# schematic.net
KiCad netlist of a schematic drawn in EAGLE
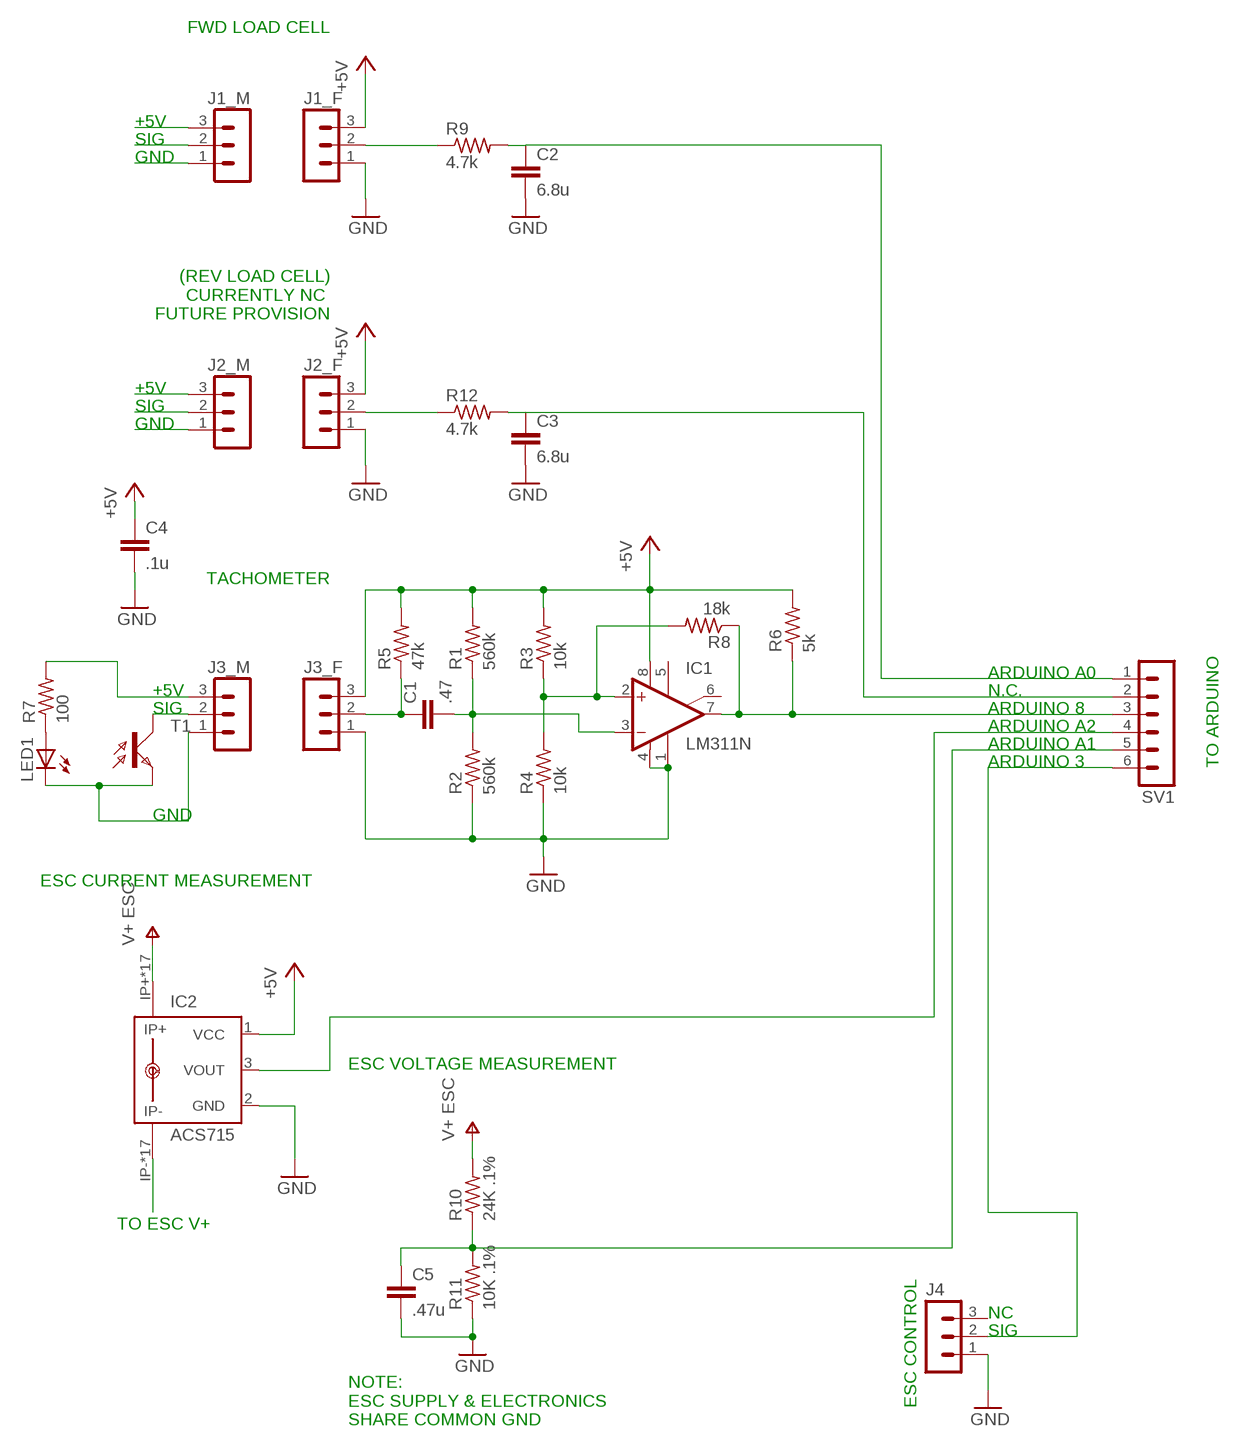
[diagram p0: schematic, sheet 1]

(export (version "E")
  (design (tool "Eeschema 10.0.6"))
  (components
    (comp (ref "C1")
      (value ".47")
      (footprint "eagle-import:C7.5B4")
      (libsource (lib "eagle-import") (part "C7.5/4"))
    )
    (comp (ref "C2")
      (value "6.8u")
      (footprint "eagle-import:C7.5B4")
      (libsource (lib "eagle-import") (part "C7.5/4"))
    )
    (comp (ref "C3")
      (value "6.8u")
      (footprint "eagle-import:C7.5B4")
      (libsource (lib "eagle-import") (part "C7.5/4"))
    )
    (comp (ref "C4")
      (value ".1u")
      (footprint "eagle-import:C7.5B4")
      (libsource (lib "eagle-import") (part "C7.5/4"))
    )
    (comp (ref "C5")
      (value ".47u")
      (footprint "eagle-import:C7.5B4")
      (libsource (lib "eagle-import") (part "C7.5/4"))
    )
    (comp (ref "IC1")
      (value "LM311N")
      (footprint "eagle-import:DIL08")
      (libsource (lib "eagle-import") (part "LM311N"))
    )
    (comp (ref "IC2")
      (value "ACS715")
      (footprint "eagle-import:ACS75050")
      (fields (field (name "MF") "ALLEGRO MICROSYSTEMS, INC.") (field (name "MPN") "ACS750LCA-050"))
      (libsource (lib "eagle-import") (part "ACS750CA-050L"))
    )
    (comp (ref "J1_F")
      (value "MA03-1")
      (footprint "eagle-import:MA03-1")
      (libsource (lib "eagle-import") (part "MA03-1"))
    )
    (comp (ref "J1_M")
      (value "MA03-1")
      (footprint "eagle-import:MA03-1")
      (libsource (lib "eagle-import") (part "MA03-1"))
    )
    (comp (ref "J2_F")
      (value "MA03-1")
      (footprint "eagle-import:MA03-1")
      (libsource (lib "eagle-import") (part "MA03-1"))
    )
    (comp (ref "J2_M")
      (value "MA03-1")
      (footprint "eagle-import:MA03-1")
      (libsource (lib "eagle-import") (part "MA03-1"))
    )
    (comp (ref "J3_F")
      (value "MA03-1")
      (footprint "eagle-import:MA03-1")
      (libsource (lib "eagle-import") (part "MA03-1"))
    )
    (comp (ref "J3_M")
      (value "MA03-1")
      (footprint "eagle-import:MA03-1")
      (libsource (lib "eagle-import") (part "MA03-1"))
    )
    (comp (ref "J4")
      (value "MA03-1")
      (footprint "eagle-import:MA03-1")
      (libsource (lib "eagle-import") (part "MA03-1"))
    )
    (comp (ref "LED1")
      (value "LAP4-BOTTOM")
      (footprint "eagle-import:P47F-BOTTOM")
      (libsource (lib "eagle-import") (part "P4-BOTTOMLA"))
    )
    (comp (ref "R1")
      (value "560k")
      (footprint "eagle-import:0207_10")
      (libsource (lib "eagle-import") (part "R-US_0207/10"))
    )
    (comp (ref "R2")
      (value "560k")
      (footprint "eagle-import:0207_10")
      (libsource (lib "eagle-import") (part "R-US_0207/10"))
    )
    (comp (ref "R3")
      (value "10k")
      (footprint "eagle-import:0207_10")
      (libsource (lib "eagle-import") (part "R-US_0207/10"))
    )
    (comp (ref "R4")
      (value "10k")
      (footprint "eagle-import:0207_10")
      (libsource (lib "eagle-import") (part "R-US_0207/10"))
    )
    (comp (ref "R5")
      (value "47k")
      (footprint "eagle-import:0207_10")
      (libsource (lib "eagle-import") (part "R-US_0207/10"))
    )
    (comp (ref "R6")
      (value "5k")
      (footprint "eagle-import:0207_10")
      (libsource (lib "eagle-import") (part "R-US_0207/10"))
    )
    (comp (ref "R7")
      (value "100")
      (footprint "eagle-import:0207_10")
      (libsource (lib "eagle-import") (part "R-US_0207/10"))
    )
    (comp (ref "R8")
      (value "18k")
      (footprint "eagle-import:0207_10")
      (libsource (lib "eagle-import") (part "R-US_0207/10"))
    )
    (comp (ref "R9")
      (value "4.7k")
      (footprint "eagle-import:0207_10")
      (libsource (lib "eagle-import") (part "R-US_0207/10"))
    )
    (comp (ref "R10")
      (value "24K .1%")
      (footprint "eagle-import:0207_10")
      (libsource (lib "eagle-import") (part "R-US_0207/10"))
    )
    (comp (ref "R11")
      (value "10K .1%")
      (footprint "eagle-import:0207_10")
      (libsource (lib "eagle-import") (part "R-US_0207/10"))
    )
    (comp (ref "R12")
      (value "4.7k")
      (footprint "eagle-import:0207_10")
      (libsource (lib "eagle-import") (part "R-US_0207/10"))
    )
    (comp (ref "SV1")
      (value "MA06-1")
      (footprint "eagle-import:MA06-1")
      (libsource (lib "eagle-import") (part "MA06-1"))
    )
    (comp (ref "T1")
      (value "BPX81")
      (footprint "eagle-import:BPX81")
      (libsource (lib "eagle-import") (part "BPX81"))
    )
  )
  (nets
    (net (code "1") (name "+5V") (class "Default")
      (node (ref "C4") (pin "1") (pinfunction "1_1") (pintype "passive"))
      (node (ref "IC1") (pin "8") (pinfunction "V+_8") (pintype "power_in"))
      (node (ref "IC2") (pin "1") (pinfunction "VCC_1") (pintype "power_in"))
      (node (ref "J1_F") (pin "3") (pinfunction "3_3") (pintype "passive"))
      (node (ref "J2_F") (pin "3") (pinfunction "3_3") (pintype "passive"))
      (node (ref "J3_F") (pin "3") (pinfunction "3_3") (pintype "passive"))
      (node (ref "R1") (pin "2") (pinfunction "2_2") (pintype "passive"))
      (node (ref "R3") (pin "2") (pinfunction "2_2") (pintype "passive"))
      (node (ref "R5") (pin "2") (pinfunction "2_2") (pintype "passive"))
      (node (ref "R6") (pin "2") (pinfunction "2_2") (pintype "passive"))
    )
    (net (code "2") (name "GND") (class "Default")
      (node (ref "C2") (pin "2") (pinfunction "2_2") (pintype "passive"))
      (node (ref "C3") (pin "2") (pinfunction "2_2") (pintype "passive"))
      (node (ref "C4") (pin "2") (pinfunction "2_2") (pintype "passive"))
      (node (ref "C5") (pin "2") (pinfunction "2_2") (pintype "passive"))
      (node (ref "IC1") (pin "1") (pinfunction "GND_1") (pintype "passive"))
      (node (ref "IC1") (pin "4") (pinfunction "V-_4") (pintype "power_in"))
      (node (ref "IC2") (pin "2") (pinfunction "GND_2") (pintype "power_in"))
      (node (ref "J1_F") (pin "1") (pinfunction "1_1") (pintype "passive"))
      (node (ref "J2_F") (pin "1") (pinfunction "1_1") (pintype "passive"))
      (node (ref "J3_F") (pin "1") (pinfunction "1_1") (pintype "passive"))
      (node (ref "J4") (pin "1") (pinfunction "1_1") (pintype "passive"))
      (node (ref "R11") (pin "1") (pinfunction "1_1") (pintype "passive"))
      (node (ref "R2") (pin "1") (pinfunction "1_1") (pintype "passive"))
      (node (ref "R4") (pin "1") (pinfunction "1_1") (pintype "passive"))
    )
    (net (code "3") (name "Net-(C1-Pad1)") (class "Default")
      (node (ref "C1") (pin "1") (pinfunction "1_1") (pintype "passive"))
      (node (ref "J3_F") (pin "2") (pinfunction "2_2") (pintype "passive"))
      (node (ref "R5") (pin "1") (pinfunction "1_1") (pintype "passive"))
    )
    (net (code "4") (name "Net-(C2-Pad1)") (class "Default")
      (node (ref "C2") (pin "1") (pinfunction "1_1") (pintype "passive"))
      (node (ref "R9") (pin "2") (pinfunction "2_2") (pintype "passive"))
      (node (ref "SV1") (pin "1") (pinfunction "1_1") (pintype "passive"))
    )
    (net (code "5") (name "Net-(C3-Pad1)") (class "Default")
      (node (ref "C3") (pin "1") (pinfunction "1_1") (pintype "passive"))
      (node (ref "R12") (pin "2") (pinfunction "2_2") (pintype "passive"))
      (node (ref "SV1") (pin "2") (pinfunction "2_2") (pintype "passive"))
    )
    (net (code "6") (name "Net-(C5-Pad1)") (class "Default")
      (node (ref "C5") (pin "1") (pinfunction "1_1") (pintype "passive"))
      (node (ref "R10") (pin "1") (pinfunction "1_1") (pintype "passive"))
      (node (ref "R11") (pin "2") (pinfunction "2_2") (pintype "passive"))
      (node (ref "SV1") (pin "5") (pinfunction "5_5") (pintype "passive"))
    )
    (net (code "7") (name "Net-(IC1-+IN)") (class "Default")
      (node (ref "IC1") (pin "2") (pinfunction "+IN_2") (pintype "input"))
      (node (ref "R3") (pin "1") (pinfunction "1_1") (pintype "passive"))
      (node (ref "R4") (pin "2") (pinfunction "2_2") (pintype "passive"))
      (node (ref "R8") (pin "2") (pinfunction "2_2") (pintype "passive"))
    )
    (net (code "8") (name "Net-(IC1--IN)") (class "Default")
      (node (ref "C1") (pin "2") (pinfunction "2_2") (pintype "passive"))
      (node (ref "IC1") (pin "3") (pinfunction "-IN_3") (pintype "input"))
      (node (ref "R1") (pin "1") (pinfunction "1_1") (pintype "passive"))
      (node (ref "R2") (pin "2") (pinfunction "2_2") (pintype "passive"))
    )
    (net (code "9") (name "Net-(IC1-OUT)") (class "Default")
      (node (ref "IC1") (pin "7") (pinfunction "OUT_7") (pintype "output"))
      (node (ref "R6") (pin "1") (pinfunction "1_1") (pintype "passive"))
      (node (ref "R8") (pin "1") (pinfunction "1_1") (pintype "passive"))
      (node (ref "SV1") (pin "3") (pinfunction "3_3") (pintype "passive"))
    )
    (net (code "10") (name "Net-(IC2-IP--PadIP-@10)") (class "Default")
      (node (ref "IC2") (pin "IP-") (pinfunction "IP-_IP-") (pintype "passive"))
      (node (ref "IC2") (pin "IP-@10") (pinfunction "IP-_IP-@10") (pintype "passive"))
      (node (ref "IC2") (pin "IP-@11") (pinfunction "IP-_IP-@11") (pintype "passive"))
      (node (ref "IC2") (pin "IP-@12") (pinfunction "IP-_IP-@12") (pintype "passive"))
      (node (ref "IC2") (pin "IP-@13") (pinfunction "IP-_IP-@13") (pintype "passive"))
      (node (ref "IC2") (pin "IP-@14") (pinfunction "IP-_IP-@14") (pintype "passive"))
      (node (ref "IC2") (pin "IP-@15") (pinfunction "IP-_IP-@15") (pintype "passive"))
      (node (ref "IC2") (pin "IP-@16") (pinfunction "IP-_IP-@16") (pintype "passive"))
      (node (ref "IC2") (pin "IP-@17") (pinfunction "IP-_IP-@17") (pintype "passive"))
      (node (ref "IC2") (pin "IP-@2") (pinfunction "IP-_IP-@2") (pintype "passive"))
      (node (ref "IC2") (pin "IP-@3") (pinfunction "IP-_IP-@3") (pintype "passive"))
      (node (ref "IC2") (pin "IP-@4") (pinfunction "IP-_IP-@4") (pintype "passive"))
      (node (ref "IC2") (pin "IP-@5") (pinfunction "IP-_IP-@5") (pintype "passive"))
      (node (ref "IC2") (pin "IP-@6") (pinfunction "IP-_IP-@6") (pintype "passive"))
      (node (ref "IC2") (pin "IP-@7") (pinfunction "IP-_IP-@7") (pintype "passive"))
      (node (ref "IC2") (pin "IP-@8") (pinfunction "IP-_IP-@8") (pintype "passive"))
      (node (ref "IC2") (pin "IP-@9") (pinfunction "IP-_IP-@9") (pintype "passive"))
    )
    (net (code "11") (name "Net-(IC2-VOUT)") (class "Default")
      (node (ref "IC2") (pin "3") (pinfunction "VOUT_3") (pintype "output"))
      (node (ref "SV1") (pin "4") (pinfunction "4_4") (pintype "passive"))
    )
    (net (code "12") (name "Net-(J1_F-Pad2)") (class "Default")
      (node (ref "J1_F") (pin "2") (pinfunction "2_2") (pintype "passive"))
      (node (ref "R9") (pin "1") (pinfunction "1_1") (pintype "passive"))
    )
    (net (code "13") (name "Net-(J2_F-Pad2)") (class "Default")
      (node (ref "J2_F") (pin "2") (pinfunction "2_2") (pintype "passive"))
      (node (ref "R12") (pin "1") (pinfunction "1_1") (pintype "passive"))
    )
    (net (code "14") (name "Net-(J3_M-Pad1)") (class "Default")
      (node (ref "J3_M") (pin "1") (pinfunction "1_1") (pintype "passive"))
      (node (ref "LED1") (pin "C") (pinfunction "C_C") (pintype "passive"))
      (node (ref "T1") (pin "E") (pinfunction "E_E") (pintype "passive"))
    )
    (net (code "15") (name "Net-(J3_M-Pad2)") (class "Default")
      (node (ref "J3_M") (pin "2") (pinfunction "2_2") (pintype "passive"))
      (node (ref "T1") (pin "C") (pinfunction "C_C") (pintype "passive"))
    )
    (net (code "16") (name "Net-(J3_M-Pad3)") (class "Default")
      (node (ref "J3_M") (pin "3") (pinfunction "3_3") (pintype "passive"))
      (node (ref "R7") (pin "2") (pinfunction "2_2") (pintype "passive"))
    )
    (net (code "17") (name "Net-(J4-Pad2)") (class "Default")
      (node (ref "J4") (pin "2") (pinfunction "2_2") (pintype "passive"))
      (node (ref "SV1") (pin "6") (pinfunction "6_6") (pintype "passive"))
    )
    (net (code "18") (name "Net-(LED1-PadA)") (class "Default")
      (node (ref "LED1") (pin "A") (pinfunction "A_A") (pintype "passive"))
      (node (ref "R7") (pin "1") (pinfunction "1_1") (pintype "passive"))
    )
    (net (code "19") (name "V+ ESC") (class "Default")
      (node (ref "IC2") (pin "IP+") (pinfunction "IP+_IP+") (pintype "passive"))
      (node (ref "IC2") (pin "IP+@10") (pinfunction "IP+_IP+@10") (pintype "passive"))
      (node (ref "IC2") (pin "IP+@11") (pinfunction "IP+_IP+@11") (pintype "passive"))
      (node (ref "IC2") (pin "IP+@12") (pinfunction "IP+_IP+@12") (pintype "passive"))
      (node (ref "IC2") (pin "IP+@13") (pinfunction "IP+_IP+@13") (pintype "passive"))
      (node (ref "IC2") (pin "IP+@14") (pinfunction "IP+_IP+@14") (pintype "passive"))
      (node (ref "IC2") (pin "IP+@15") (pinfunction "IP+_IP+@15") (pintype "passive"))
      (node (ref "IC2") (pin "IP+@16") (pinfunction "IP+_IP+@16") (pintype "passive"))
      (node (ref "IC2") (pin "IP+@17") (pinfunction "IP+_IP+@17") (pintype "passive"))
      (node (ref "IC2") (pin "IP+@2") (pinfunction "IP+_IP+@2") (pintype "passive"))
      (node (ref "IC2") (pin "IP+@3") (pinfunction "IP+_IP+@3") (pintype "passive"))
      (node (ref "IC2") (pin "IP+@4") (pinfunction "IP+_IP+@4") (pintype "passive"))
      (node (ref "IC2") (pin "IP+@5") (pinfunction "IP+_IP+@5") (pintype "passive"))
      (node (ref "IC2") (pin "IP+@6") (pinfunction "IP+_IP+@6") (pintype "passive"))
      (node (ref "IC2") (pin "IP+@7") (pinfunction "IP+_IP+@7") (pintype "passive"))
      (node (ref "IC2") (pin "IP+@8") (pinfunction "IP+_IP+@8") (pintype "passive"))
      (node (ref "IC2") (pin "IP+@9") (pinfunction "IP+_IP+@9") (pintype "passive"))
      (node (ref "R10") (pin "2") (pinfunction "2_2") (pintype "passive"))
    )
    (net (code "20") (name "unconnected-(IC1-ON-Pad5)") (class "Default")
      (node (ref "IC1") (pin "5") (pinfunction "ON_5") (pintype "passive"))
    )
    (net (code "21") (name "unconnected-(IC1-ON{slash}STR-Pad6)") (class "Default")
      (node (ref "IC1") (pin "6") (pinfunction "ON/STR_6") (pintype "passive"))
    )
    (net (code "22") (name "unconnected-(J1_M-Pad1)") (class "Default")
      (node (ref "J1_M") (pin "1") (pinfunction "1_1") (pintype "passive"))
    )
    (net (code "23") (name "unconnected-(J1_M-Pad2)") (class "Default")
      (node (ref "J1_M") (pin "2") (pinfunction "2_2") (pintype "passive"))
    )
    (net (code "24") (name "unconnected-(J1_M-Pad3)") (class "Default")
      (node (ref "J1_M") (pin "3") (pinfunction "3_3") (pintype "passive"))
    )
    (net (code "25") (name "unconnected-(J2_M-Pad1)") (class "Default")
      (node (ref "J2_M") (pin "1") (pinfunction "1_1") (pintype "passive"))
    )
    (net (code "26") (name "unconnected-(J2_M-Pad2)") (class "Default")
      (node (ref "J2_M") (pin "2") (pinfunction "2_2") (pintype "passive"))
    )
    (net (code "27") (name "unconnected-(J2_M-Pad3)") (class "Default")
      (node (ref "J2_M") (pin "3") (pinfunction "3_3") (pintype "passive"))
    )
    (net (code "28") (name "unconnected-(J4-Pad3)") (class "Default")
      (node (ref "J4") (pin "3") (pinfunction "3_3") (pintype "passive"))
    )
  )
)
